# noiseometer_v1.net
KiCad netlist of a schematic drawn in EAGLE
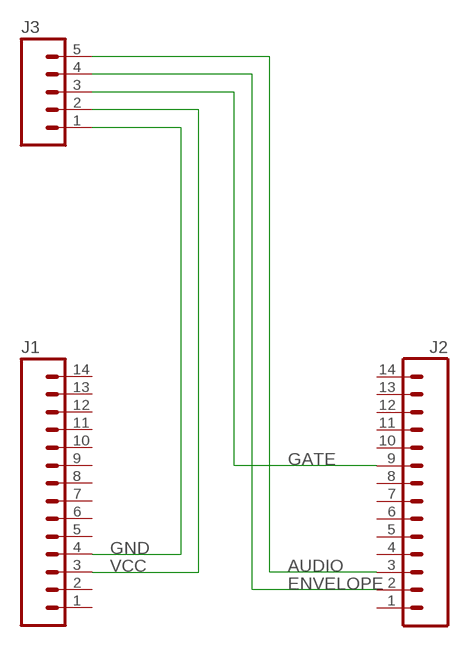
[diagram p0: schematic, sheet 1]

(export (version "E")
  (design (tool "Eeschema 10.0.6"))
  (components
    (comp (ref "J1")
      (value "M14")
      (footprint "eagle-import:1X14")
      (libsource (lib "eagle-import") (part "M14"))
    )
    (comp (ref "J2")
      (value "M14")
      (footprint "eagle-import:1X14")
      (libsource (lib "eagle-import") (part "M14"))
    )
    (comp (ref "J3")
      (value "M05PTH")
      (footprint "eagle-import:1X05")
      (libsource (lib "eagle-import") (part "M05PTH"))
    )
  )
  (nets
    (net (code "1") (name "/AUDIO") (class "Default")
      (node (ref "J2") (pin "3") (pinfunction "3_3") (pintype "passive"))
      (node (ref "J3") (pin "5") (pinfunction "5_5") (pintype "passive"))
    )
    (net (code "2") (name "/ENVELOPE") (class "Default")
      (node (ref "J2") (pin "2") (pinfunction "2_2") (pintype "passive"))
      (node (ref "J3") (pin "4") (pinfunction "4_4") (pintype "passive"))
    )
    (net (code "3") (name "/GATE") (class "Default")
      (node (ref "J2") (pin "9") (pinfunction "9_9") (pintype "passive"))
      (node (ref "J3") (pin "3") (pinfunction "3_3") (pintype "passive"))
    )
    (net (code "4") (name "/GND") (class "Default")
      (node (ref "J1") (pin "4") (pinfunction "4_4") (pintype "passive"))
      (node (ref "J3") (pin "1") (pinfunction "1_1") (pintype "passive"))
    )
    (net (code "5") (name "/VCC") (class "Default")
      (node (ref "J1") (pin "3") (pinfunction "3_3") (pintype "passive"))
      (node (ref "J3") (pin "2") (pinfunction "2_2") (pintype "passive"))
    )
    (net (code "6") (name "unconnected-(J1-Pad1)") (class "Default")
      (node (ref "J1") (pin "1") (pinfunction "1_1") (pintype "passive"))
    )
    (net (code "7") (name "unconnected-(J1-Pad2)") (class "Default")
      (node (ref "J1") (pin "2") (pinfunction "2_2") (pintype "passive"))
    )
    (net (code "8") (name "unconnected-(J1-Pad5)") (class "Default")
      (node (ref "J1") (pin "5") (pinfunction "5_5") (pintype "passive"))
    )
    (net (code "9") (name "unconnected-(J1-Pad6)") (class "Default")
      (node (ref "J1") (pin "6") (pinfunction "6_6") (pintype "passive"))
    )
    (net (code "10") (name "unconnected-(J1-Pad7)") (class "Default")
      (node (ref "J1") (pin "7") (pinfunction "7_7") (pintype "passive"))
    )
    (net (code "11") (name "unconnected-(J1-Pad8)") (class "Default")
      (node (ref "J1") (pin "8") (pinfunction "8_8") (pintype "passive"))
    )
    (net (code "12") (name "unconnected-(J1-Pad9)") (class "Default")
      (node (ref "J1") (pin "9") (pinfunction "9_9") (pintype "passive"))
    )
    (net (code "13") (name "unconnected-(J1-Pad10)") (class "Default")
      (node (ref "J1") (pin "10") (pinfunction "10_10") (pintype "passive"))
    )
    (net (code "14") (name "unconnected-(J1-Pad11)") (class "Default")
      (node (ref "J1") (pin "11") (pinfunction "11_11") (pintype "passive"))
    )
    (net (code "15") (name "unconnected-(J1-Pad12)") (class "Default")
      (node (ref "J1") (pin "12") (pinfunction "12_12") (pintype "passive"))
    )
    (net (code "16") (name "unconnected-(J1-Pad13)") (class "Default")
      (node (ref "J1") (pin "13") (pinfunction "13_13") (pintype "passive"))
    )
    (net (code "17") (name "unconnected-(J1-Pad14)") (class "Default")
      (node (ref "J1") (pin "14") (pinfunction "14_14") (pintype "passive"))
    )
    (net (code "18") (name "unconnected-(J2-Pad1)") (class "Default")
      (node (ref "J2") (pin "1") (pinfunction "1_1") (pintype "passive"))
    )
    (net (code "19") (name "unconnected-(J2-Pad4)") (class "Default")
      (node (ref "J2") (pin "4") (pinfunction "4_4") (pintype "passive"))
    )
    (net (code "20") (name "unconnected-(J2-Pad5)") (class "Default")
      (node (ref "J2") (pin "5") (pinfunction "5_5") (pintype "passive"))
    )
    (net (code "21") (name "unconnected-(J2-Pad6)") (class "Default")
      (node (ref "J2") (pin "6") (pinfunction "6_6") (pintype "passive"))
    )
    (net (code "22") (name "unconnected-(J2-Pad7)") (class "Default")
      (node (ref "J2") (pin "7") (pinfunction "7_7") (pintype "passive"))
    )
    (net (code "23") (name "unconnected-(J2-Pad8)") (class "Default")
      (node (ref "J2") (pin "8") (pinfunction "8_8") (pintype "passive"))
    )
    (net (code "24") (name "unconnected-(J2-Pad10)") (class "Default")
      (node (ref "J2") (pin "10") (pinfunction "10_10") (pintype "passive"))
    )
    (net (code "25") (name "unconnected-(J2-Pad11)") (class "Default")
      (node (ref "J2") (pin "11") (pinfunction "11_11") (pintype "passive"))
    )
    (net (code "26") (name "unconnected-(J2-Pad12)") (class "Default")
      (node (ref "J2") (pin "12") (pinfunction "12_12") (pintype "passive"))
    )
    (net (code "27") (name "unconnected-(J2-Pad13)") (class "Default")
      (node (ref "J2") (pin "13") (pinfunction "13_13") (pintype "passive"))
    )
    (net (code "28") (name "unconnected-(J2-Pad14)") (class "Default")
      (node (ref "J2") (pin "14") (pinfunction "14_14") (pintype "passive"))
    )
  )
)
